# imu_v2_side.net
KiCad netlist of a schematic drawn in EAGLE
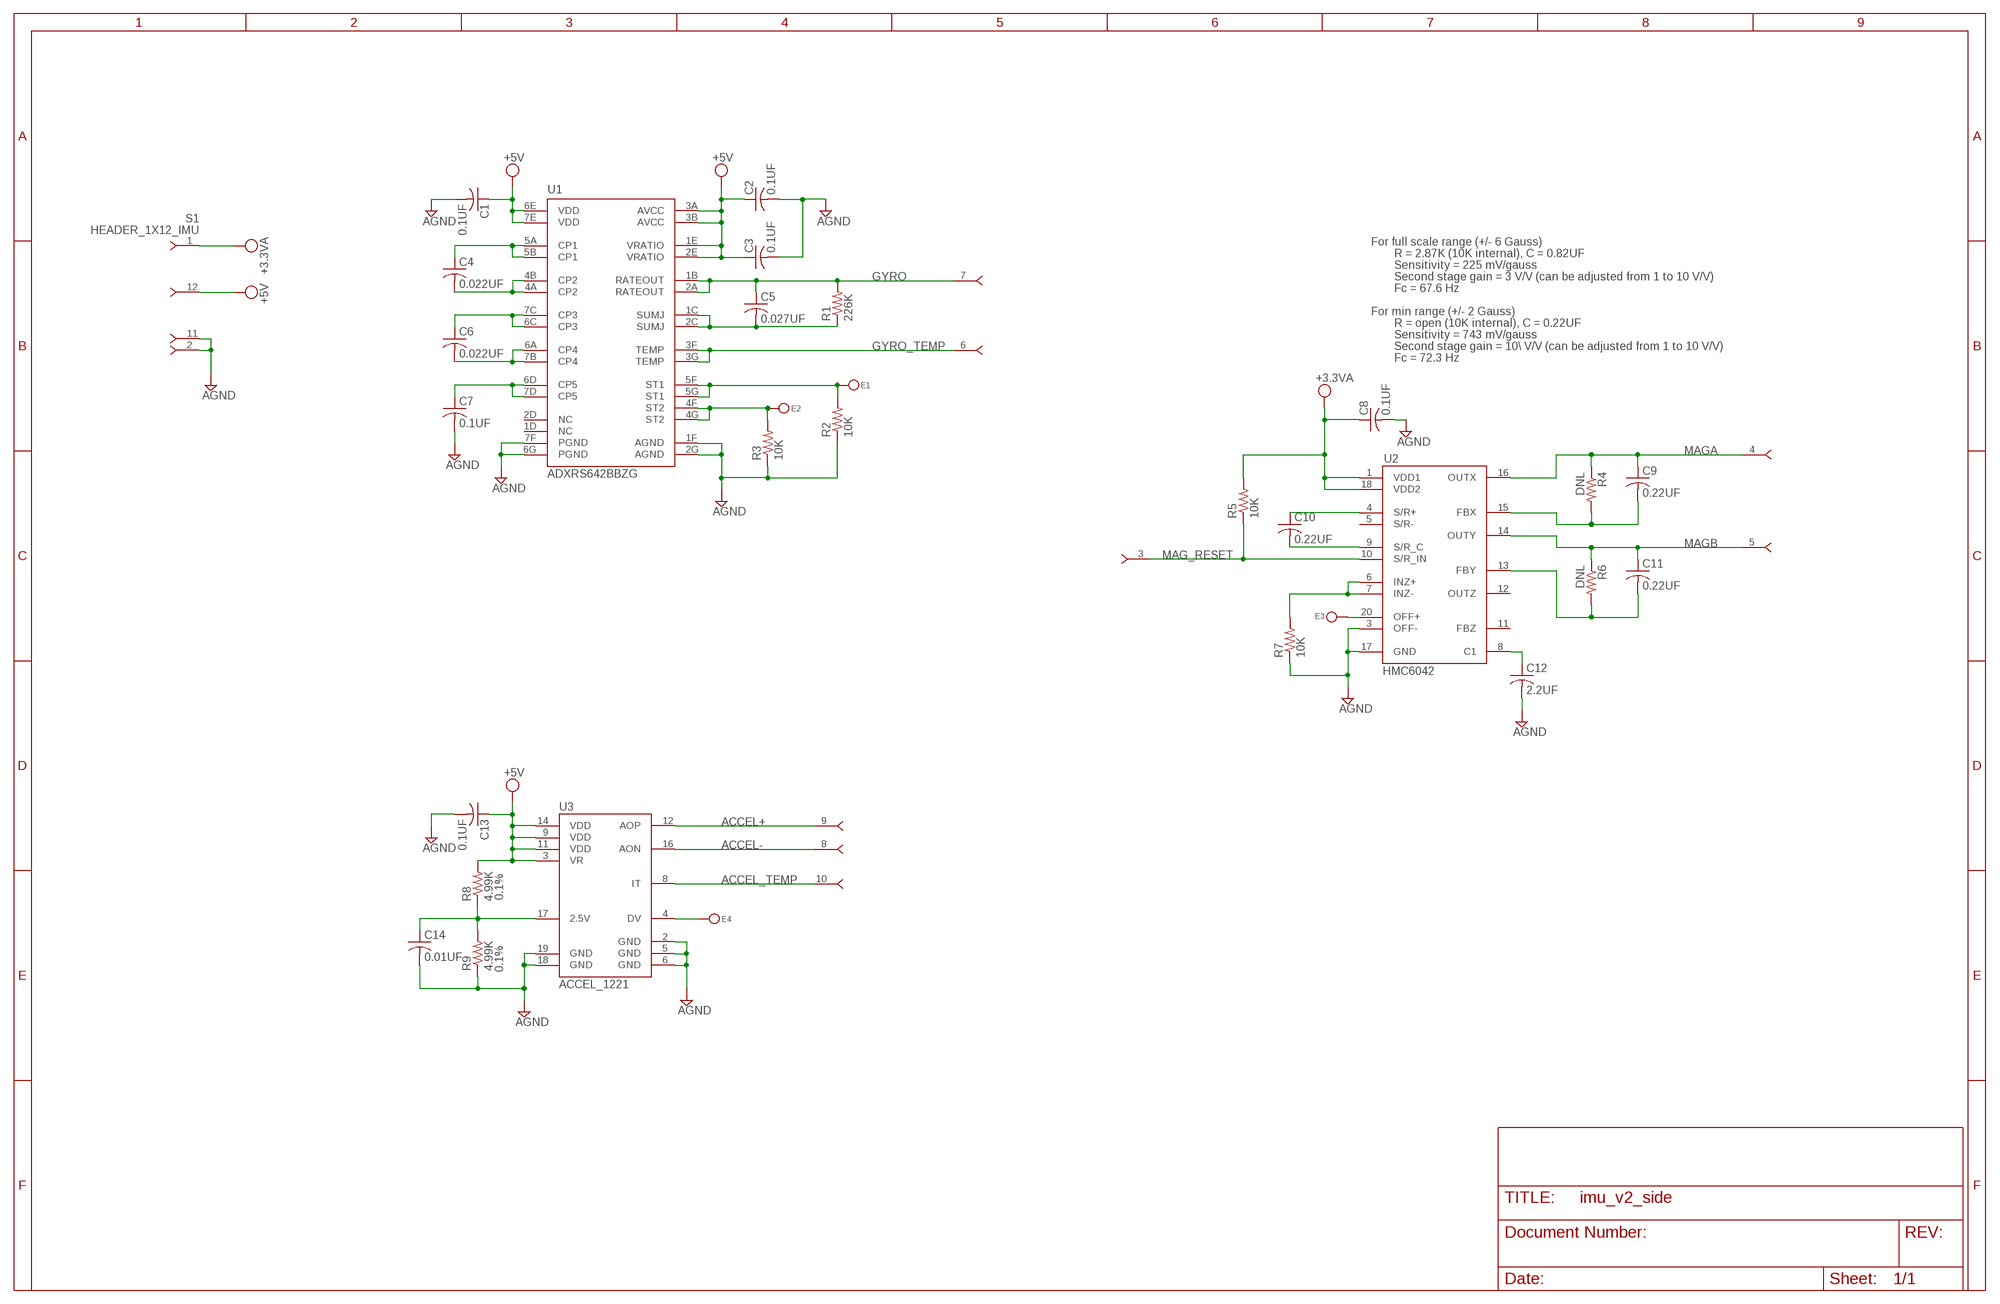
[diagram p0: schematic, sheet 1]

(export (version "E")
  (design (tool "Eeschema 10.0.6"))
  (components
    (comp (ref "C1")
      (value "0.1UF")
      (footprint "eagle-import:C0603K")
      (libsource (lib "eagle-import") (part "C-USC0603K"))
    )
    (comp (ref "C2")
      (value "0.1UF")
      (footprint "eagle-import:C0603K")
      (libsource (lib "eagle-import") (part "C-USC0603K"))
    )
    (comp (ref "C3")
      (value "0.1UF")
      (footprint "eagle-import:C0603K")
      (libsource (lib "eagle-import") (part "C-USC0603K"))
    )
    (comp (ref "C4")
      (value "0.022UF")
      (footprint "eagle-import:C0603K")
      (libsource (lib "eagle-import") (part "C-USC0603K"))
    )
    (comp (ref "C5")
      (value "0.027UF")
      (footprint "eagle-import:C0603K")
      (libsource (lib "eagle-import") (part "C-USC0603K"))
    )
    (comp (ref "C6")
      (value "0.022UF")
      (footprint "eagle-import:C0603K")
      (libsource (lib "eagle-import") (part "C-USC0603K"))
    )
    (comp (ref "C7")
      (value "0.1UF")
      (footprint "eagle-import:C0603K")
      (libsource (lib "eagle-import") (part "C-USC0603K"))
    )
    (comp (ref "C8")
      (value "0.1UF")
      (footprint "eagle-import:C0603K")
      (libsource (lib "eagle-import") (part "C-USC0603K"))
    )
    (comp (ref "C9")
      (value "0.22UF")
      (footprint "eagle-import:C0603K")
      (libsource (lib "eagle-import") (part "C-USC0603K"))
    )
    (comp (ref "C10")
      (value "0.22UF")
      (footprint "eagle-import:C0603K")
      (libsource (lib "eagle-import") (part "C-USC0603K"))
    )
    (comp (ref "C11")
      (value "0.22UF")
      (footprint "eagle-import:C0603K")
      (libsource (lib "eagle-import") (part "C-USC0603K"))
    )
    (comp (ref "C12")
      (value "2.2UF")
      (footprint "eagle-import:C0603K")
      (libsource (lib "eagle-import") (part "C-USC0603K"))
    )
    (comp (ref "C13")
      (value "0.1UF")
      (footprint "eagle-import:C0603K")
      (libsource (lib "eagle-import") (part "C-USC0603K"))
    )
    (comp (ref "C14")
      (value "0.01UF")
      (footprint "eagle-import:C0603K")
      (libsource (lib "eagle-import") (part "C-USC0603K"))
    )
    (comp (ref "E1")
      (value "TP30")
      (footprint "eagle-import:TP30")
      (libsource (lib "eagle-import") (part "TP30"))
    )
    (comp (ref "E2")
      (value "TP30")
      (footprint "eagle-import:TP30")
      (libsource (lib "eagle-import") (part "TP30"))
    )
    (comp (ref "E3")
      (value "TP30")
      (footprint "eagle-import:TP30")
      (libsource (lib "eagle-import") (part "TP30"))
    )
    (comp (ref "E4")
      (value "TP30")
      (footprint "eagle-import:TP30")
      (libsource (lib "eagle-import") (part "TP30"))
    )
    (comp (ref "R1")
      (value "226K")
      (footprint "eagle-import:R0603")
      (libsource (lib "eagle-import") (part "R-US_R0603"))
    )
    (comp (ref "R2")
      (value "10K")
      (footprint "eagle-import:R0603")
      (libsource (lib "eagle-import") (part "R-US_R0603"))
    )
    (comp (ref "R3")
      (value "10K")
      (footprint "eagle-import:R0603")
      (libsource (lib "eagle-import") (part "R-US_R0603"))
    )
    (comp (ref "R4")
      (value "DNL")
      (footprint "eagle-import:R0603")
      (libsource (lib "eagle-import") (part "R-US_R0603"))
    )
    (comp (ref "R5")
      (value "10K")
      (footprint "eagle-import:R0603")
      (libsource (lib "eagle-import") (part "R-US_R0603"))
    )
    (comp (ref "R6")
      (value "DNL")
      (footprint "eagle-import:R0603")
      (libsource (lib "eagle-import") (part "R-US_R0603"))
    )
    (comp (ref "R7")
      (value "10K")
      (footprint "eagle-import:R0603")
      (libsource (lib "eagle-import") (part "R-US_R0603"))
    )
    (comp (ref "R8")
      (value "4.99K")
      (footprint "eagle-import:R0603")
      (fields (field (name "TOL") "0.1%"))
      (libsource (lib "eagle-import") (part "R-US_R0603"))
    )
    (comp (ref "R9")
      (value "4.99K")
      (footprint "eagle-import:R0603")
      (fields (field (name "TOL") "0.1%"))
      (libsource (lib "eagle-import") (part "R-US_R0603"))
    )
    (comp (ref "S1")
      (value "HEADER_1X12_IMU")
      (footprint "eagle-import:HEADER_1X12_2MM_TH")
      (libsource (lib "eagle-import") (part "HEADER_1X12_IMU"))
    )
    (comp (ref "U1")
      (value "ADXRS642BBZG")
      (footprint "eagle-import:ADXRS_CBGA32")
      (libsource (lib "eagle-import") (part "ADXRSBBZG642"))
    )
    (comp (ref "U2")
      (value "HMC6042")
      (footprint "eagle-import:HMC6042_LPCC")
      (libsource (lib "eagle-import") (part "HMC6042"))
    )
    (comp (ref "U3")
      (value "ACCEL_1221")
      (footprint "eagle-import:1221_LCC")
      (libsource (lib "eagle-import") (part "ACCEL_1221"))
    )
  )
  (nets
    (net (code "1") (name "+3.3VA") (class "Default")
      (node (ref "C8") (pin "1") (pinfunction "1_1") (pintype "passive"))
      (node (ref "R5") (pin "2") (pinfunction "2_2") (pintype "passive"))
      (node (ref "S1") (pin "1") (pinfunction "P$1_1") (pintype "bidirectional"))
      (node (ref "U2") (pin "1") (pinfunction "VDD1_1") (pintype "bidirectional"))
      (node (ref "U2") (pin "18") (pinfunction "VDD2_18") (pintype "bidirectional"))
    )
    (net (code "2") (name "+5V") (class "Default")
      (node (ref "C1") (pin "1") (pinfunction "1_1") (pintype "passive"))
      (node (ref "C13") (pin "1") (pinfunction "1_1") (pintype "passive"))
      (node (ref "C2") (pin "1") (pinfunction "1_1") (pintype "passive"))
      (node (ref "C3") (pin "1") (pinfunction "1_1") (pintype "passive"))
      (node (ref "R8") (pin "2") (pinfunction "2_2") (pintype "passive"))
      (node (ref "S1") (pin "12") (pinfunction "1_12") (pintype "bidirectional"))
      (node (ref "U1") (pin "1E") (pinfunction "VRATIO_1E") (pintype "input"))
      (node (ref "U1") (pin "2E") (pinfunction "VRATIO_2E") (pintype "input"))
      (node (ref "U1") (pin "3A") (pinfunction "AVCC_3A") (pintype "bidirectional"))
      (node (ref "U1") (pin "3B") (pinfunction "AVCC_3B") (pintype "bidirectional"))
      (node (ref "U1") (pin "6E") (pinfunction "VDD_6E") (pintype "bidirectional"))
      (node (ref "U1") (pin "7E") (pinfunction "VDD_7E") (pintype "bidirectional"))
      (node (ref "U3") (pin "11") (pinfunction "VDD_11") (pintype "bidirectional"))
      (node (ref "U3") (pin "14") (pinfunction "VDD_14") (pintype "bidirectional"))
      (node (ref "U3") (pin "3") (pinfunction "VR_3") (pintype "bidirectional"))
      (node (ref "U3") (pin "9") (pinfunction "VDD_9") (pintype "bidirectional"))
    )
    (net (code "3") (name "/ACCEL+") (class "Default")
      (node (ref "S1") (pin "9") (pinfunction "1_9") (pintype "bidirectional"))
      (node (ref "U3") (pin "12") (pinfunction "AOP_12") (pintype "output"))
    )
    (net (code "4") (name "/ACCEL-") (class "Default")
      (node (ref "S1") (pin "8") (pinfunction "1_8") (pintype "bidirectional"))
      (node (ref "U3") (pin "16") (pinfunction "AON_16") (pintype "output"))
    )
    (net (code "5") (name "/ACCEL_TEMP") (class "Default")
      (node (ref "S1") (pin "10") (pinfunction "1_10") (pintype "bidirectional"))
      (node (ref "U3") (pin "8") (pinfunction "IT_8") (pintype "output"))
    )
    (net (code "6") (name "/GYRO") (class "Default")
      (node (ref "C5") (pin "1") (pinfunction "1_1") (pintype "passive"))
      (node (ref "R1") (pin "2") (pinfunction "2_2") (pintype "passive"))
      (node (ref "S1") (pin "7") (pinfunction "1_7") (pintype "bidirectional"))
      (node (ref "U1") (pin "1B") (pinfunction "RATEOUT_1B") (pintype "output"))
      (node (ref "U1") (pin "2A") (pinfunction "RATEOUT_2A") (pintype "output"))
    )
    (net (code "7") (name "/GYRO_TEMP") (class "Default")
      (node (ref "S1") (pin "6") (pinfunction "1_6") (pintype "bidirectional"))
      (node (ref "U1") (pin "3F") (pinfunction "TEMP_3F") (pintype "output"))
      (node (ref "U1") (pin "3G") (pinfunction "TEMP_3G") (pintype "output"))
    )
    (net (code "8") (name "/MAGA") (class "Default")
      (node (ref "C9") (pin "1") (pinfunction "1_1") (pintype "passive"))
      (node (ref "R4") (pin "1") (pinfunction "1_1") (pintype "passive"))
      (node (ref "S1") (pin "4") (pinfunction "1_4") (pintype "bidirectional"))
      (node (ref "U2") (pin "16") (pinfunction "OUTX_16") (pintype "output"))
    )
    (net (code "9") (name "/MAGB") (class "Default")
      (node (ref "C11") (pin "1") (pinfunction "1_1") (pintype "passive"))
      (node (ref "R6") (pin "1") (pinfunction "1_1") (pintype "passive"))
      (node (ref "S1") (pin "5") (pinfunction "1_5") (pintype "bidirectional"))
      (node (ref "U2") (pin "14") (pinfunction "OUTY_14") (pintype "output"))
    )
    (net (code "10") (name "/MAG_RESET") (class "Default")
      (node (ref "R5") (pin "1") (pinfunction "1_1") (pintype "passive"))
      (node (ref "S1") (pin "3") (pinfunction "1_3") (pintype "bidirectional"))
      (node (ref "U2") (pin "10") (pinfunction "S/R_IN_10") (pintype "input"))
    )
    (net (code "11") (name "AGND") (class "Default")
      (node (ref "C1") (pin "2") (pinfunction "2_2") (pintype "passive"))
      (node (ref "C12") (pin "2") (pinfunction "2_2") (pintype "passive"))
      (node (ref "C13") (pin "2") (pinfunction "2_2") (pintype "passive"))
      (node (ref "C14") (pin "2") (pinfunction "2_2") (pintype "passive"))
      (node (ref "C2") (pin "2") (pinfunction "2_2") (pintype "passive"))
      (node (ref "C3") (pin "2") (pinfunction "2_2") (pintype "passive"))
      (node (ref "C7") (pin "2") (pinfunction "2_2") (pintype "passive"))
      (node (ref "C8") (pin "2") (pinfunction "2_2") (pintype "passive"))
      (node (ref "R2") (pin "1") (pinfunction "1_1") (pintype "passive"))
      (node (ref "R3") (pin "1") (pinfunction "1_1") (pintype "passive"))
      (node (ref "R7") (pin "1") (pinfunction "1_1") (pintype "passive"))
      (node (ref "R9") (pin "1") (pinfunction "1_1") (pintype "passive"))
      (node (ref "S1") (pin "11") (pinfunction "1_11") (pintype "bidirectional"))
      (node (ref "S1") (pin "2") (pinfunction "1_2") (pintype "bidirectional"))
      (node (ref "U1") (pin "1F") (pinfunction "AGND_1F") (pintype "bidirectional"))
      (node (ref "U1") (pin "2G") (pinfunction "AGND_2G") (pintype "bidirectional"))
      (node (ref "U1") (pin "6G") (pinfunction "PGND_6G") (pintype "bidirectional"))
      (node (ref "U1") (pin "7F") (pinfunction "PGND_7F") (pintype "bidirectional"))
      (node (ref "U2") (pin "17") (pinfunction "GND_17") (pintype "bidirectional"))
      (node (ref "U2") (pin "3") (pinfunction "OFF-_3") (pintype "input"))
      (node (ref "U3") (pin "18") (pinfunction "GND_18") (pintype "bidirectional"))
      (node (ref "U3") (pin "19") (pinfunction "GND_19") (pintype "bidirectional"))
      (node (ref "U3") (pin "2") (pinfunction "GND_2") (pintype "bidirectional"))
      (node (ref "U3") (pin "5") (pinfunction "GND_5") (pintype "bidirectional"))
      (node (ref "U3") (pin "6") (pinfunction "GND_6") (pintype "bidirectional"))
    )
    (net (code "12") (name "Net-(C4-Pad1)") (class "Default")
      (node (ref "C4") (pin "1") (pinfunction "1_1") (pintype "passive"))
      (node (ref "U1") (pin "5A") (pinfunction "CP1_5A") (pintype "bidirectional"))
      (node (ref "U1") (pin "5B") (pinfunction "CP1_5B") (pintype "bidirectional"))
    )
    (net (code "13") (name "Net-(C4-Pad2)") (class "Default")
      (node (ref "C4") (pin "2") (pinfunction "2_2") (pintype "passive"))
      (node (ref "U1") (pin "4A") (pinfunction "CP2_4A") (pintype "bidirectional"))
      (node (ref "U1") (pin "4B") (pinfunction "CP2_4B") (pintype "bidirectional"))
    )
    (net (code "14") (name "Net-(C5-Pad2)") (class "Default")
      (node (ref "C5") (pin "2") (pinfunction "2_2") (pintype "passive"))
      (node (ref "R1") (pin "1") (pinfunction "1_1") (pintype "passive"))
      (node (ref "U1") (pin "1C") (pinfunction "SUMJ_1C") (pintype "bidirectional"))
      (node (ref "U1") (pin "2C") (pinfunction "SUMJ_2C") (pintype "bidirectional"))
    )
    (net (code "15") (name "Net-(C6-Pad1)") (class "Default")
      (node (ref "C6") (pin "1") (pinfunction "1_1") (pintype "passive"))
      (node (ref "U1") (pin "6C") (pinfunction "CP3_6C") (pintype "bidirectional"))
      (node (ref "U1") (pin "7C") (pinfunction "CP3_7C") (pintype "bidirectional"))
    )
    (net (code "16") (name "Net-(C6-Pad2)") (class "Default")
      (node (ref "C6") (pin "2") (pinfunction "2_2") (pintype "passive"))
      (node (ref "U1") (pin "6A") (pinfunction "CP4_6A") (pintype "bidirectional"))
      (node (ref "U1") (pin "7B") (pinfunction "CP4_7B") (pintype "bidirectional"))
    )
    (net (code "17") (name "Net-(C7-Pad1)") (class "Default")
      (node (ref "C7") (pin "1") (pinfunction "1_1") (pintype "passive"))
      (node (ref "U1") (pin "6D") (pinfunction "CP5_6D") (pintype "bidirectional"))
      (node (ref "U1") (pin "7D") (pinfunction "CP5_7D") (pintype "bidirectional"))
    )
    (net (code "18") (name "Net-(E1-Pad1)") (class "Default")
      (node (ref "E1") (pin "1") (pinfunction "1_1") (pintype "bidirectional"))
      (node (ref "R2") (pin "2") (pinfunction "2_2") (pintype "passive"))
      (node (ref "U1") (pin "5F") (pinfunction "ST1_5F") (pintype "input"))
      (node (ref "U1") (pin "5G") (pinfunction "ST1_5G") (pintype "input"))
    )
    (net (code "19") (name "Net-(E2-Pad1)") (class "Default")
      (node (ref "E2") (pin "1") (pinfunction "1_1") (pintype "bidirectional"))
      (node (ref "R3") (pin "2") (pinfunction "2_2") (pintype "passive"))
      (node (ref "U1") (pin "4F") (pinfunction "ST2_4F") (pintype "input"))
      (node (ref "U1") (pin "4G") (pinfunction "ST2_4G") (pintype "input"))
    )
    (net (code "20") (name "Net-(U2-C1)") (class "Default")
      (node (ref "C12") (pin "1") (pinfunction "1_1") (pintype "passive"))
      (node (ref "U2") (pin "8") (pinfunction "C1_8") (pintype "bidirectional"))
    )
    (net (code "21") (name "Net-(U2-FBX)") (class "Default")
      (node (ref "C9") (pin "2") (pinfunction "2_2") (pintype "passive"))
      (node (ref "R4") (pin "2") (pinfunction "2_2") (pintype "passive"))
      (node (ref "U2") (pin "15") (pinfunction "FBX_15") (pintype "bidirectional"))
    )
    (net (code "22") (name "Net-(U2-FBY)") (class "Default")
      (node (ref "C11") (pin "2") (pinfunction "2_2") (pintype "passive"))
      (node (ref "R6") (pin "2") (pinfunction "2_2") (pintype "passive"))
      (node (ref "U2") (pin "13") (pinfunction "FBY_13") (pintype "bidirectional"))
    )
    (net (code "23") (name "Net-(U2-INZ+)") (class "Default")
      (node (ref "R7") (pin "2") (pinfunction "2_2") (pintype "passive"))
      (node (ref "U2") (pin "6") (pinfunction "INZ+_6") (pintype "input"))
      (node (ref "U2") (pin "7") (pinfunction "INZ-_7") (pintype "input"))
    )
    (net (code "24") (name "Net-(U2-OFF+)") (class "Default")
      (node (ref "E3") (pin "1") (pinfunction "1_1") (pintype "bidirectional"))
      (node (ref "U2") (pin "20") (pinfunction "OFF+_20") (pintype "input"))
    )
    (net (code "25") (name "Net-(U2-S{slash}R+)") (class "Default")
      (node (ref "C10") (pin "1") (pinfunction "1_1") (pintype "passive"))
      (node (ref "U2") (pin "4") (pinfunction "S/R+_4") (pintype "bidirectional"))
    )
    (net (code "26") (name "Net-(U2-S{slash}R_C)") (class "Default")
      (node (ref "C10") (pin "2") (pinfunction "2_2") (pintype "passive"))
      (node (ref "U2") (pin "9") (pinfunction "S/R_C_9") (pintype "bidirectional"))
    )
    (net (code "27") (name "Net-(U3-2.5V)") (class "Default")
      (node (ref "C14") (pin "1") (pinfunction "1_1") (pintype "passive"))
      (node (ref "R8") (pin "1") (pinfunction "1_1") (pintype "passive"))
      (node (ref "R9") (pin "2") (pinfunction "2_2") (pintype "passive"))
      (node (ref "U3") (pin "17") (pinfunction "2.5V_17") (pintype "bidirectional"))
    )
    (net (code "28") (name "Net-(U3-DV)") (class "Default")
      (node (ref "E4") (pin "1") (pinfunction "1_1") (pintype "bidirectional"))
      (node (ref "U3") (pin "4") (pinfunction "DV_4") (pintype "input"))
    )
    (net (code "29") (name "unconnected-(U1-NC-Pad1D)") (class "Default")
      (node (ref "U1") (pin "1D") (pinfunction "NC_1D") (pintype "bidirectional"))
    )
    (net (code "30") (name "unconnected-(U1-NC-Pad2D)") (class "Default")
      (node (ref "U1") (pin "2D") (pinfunction "NC_2D") (pintype "bidirectional"))
    )
    (net (code "31") (name "unconnected-(U2-FBZ-Pad11)") (class "Default")
      (node (ref "U2") (pin "11") (pinfunction "FBZ_11") (pintype "bidirectional"))
    )
    (net (code "32") (name "unconnected-(U2-OUTZ-Pad12)") (class "Default")
      (node (ref "U2") (pin "12") (pinfunction "OUTZ_12") (pintype "output"))
    )
    (net (code "33") (name "unconnected-(U2-S{slash}R--Pad5)") (class "Default")
      (node (ref "U2") (pin "5") (pinfunction "S/R-_5") (pintype "bidirectional"))
    )
  )
)
